# MAIN_SCH.net
KiCad netlist of a schematic drawn in Altium Designer
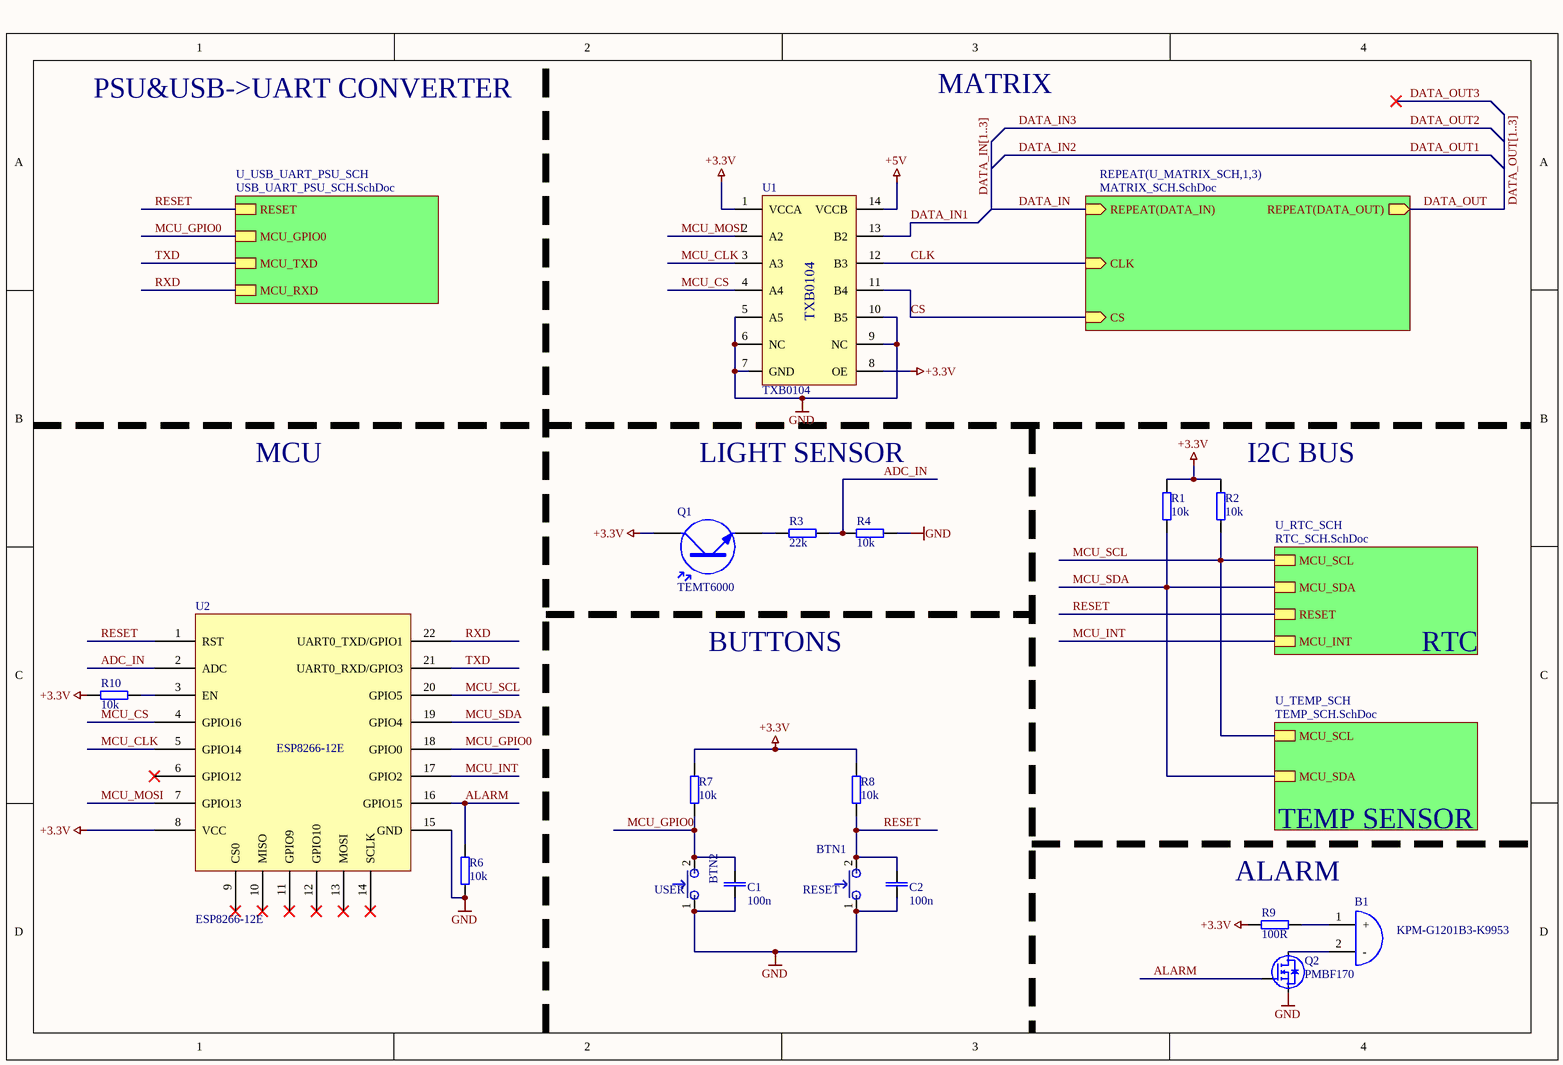
[diagram p0: MAIN_SCH.SchDoc]

(export (version "E")
  (design (tool "Eeschema 10.0.6"))
  (components
    (comp (ref "B1")
      (value "KPM-G1201B3-K9953")
      (footprint "KPM-G1201B3-K9953")
      (description "BUZZER")
      (libsource (lib "SCH_LIB") (part "BUZZER"))
    )
    (comp (ref "BTN1")
      (value "USER")
      (footprint "PBUTTON_SMD")
      (description "Tactile push button")
      (libsource (lib "SCH_LIB") (part "PUSHBUTTON"))
    )
    (comp (ref "BTN2")
      (value "RESET")
      (footprint "PBUTTON_SMD")
      (description "Tactile push button")
      (libsource (lib "SCH_LIB") (part "PUSHBUTTON"))
    )
    (comp (ref "C1")
      (value "100n")
      (footprint "CAP 0805")
      (description "NON POLARIZED CAPACITOR")
      (libsource (lib "SCH_LIB") (part "CAP"))
    )
    (comp (ref "C2")
      (value "100n")
      (footprint "CAP 0805")
      (description "NON POLARIZED CAPACITOR")
      (libsource (lib "SCH_LIB") (part "CAP"))
    )
    (comp (ref "Q1")
      (value "TEMT6000")
      (footprint "TEMT600")
      (description "Light sensor")
      (libsource (lib "SCH_LIB") (part "TEMT6000"))
    )
    (comp (ref "Q2")
      (value "PMBF170")
      (footprint "SOT23")
      (description "N-Channel MOSFET")
      (libsource (lib "SCH_LIB") (part "PMBF170"))
    )
    (comp (ref "R1")
      (value "10k")
      (footprint "RES 0805")
      (description "RESISTOR")
      (libsource (lib "SCH_LIB") (part "RES"))
    )
    (comp (ref "R2")
      (value "10k")
      (footprint "RES 0805")
      (description "RESISTOR")
      (libsource (lib "SCH_LIB") (part "RES"))
    )
    (comp (ref "R3")
      (value "22k")
      (footprint "RES 0805")
      (description "RESISTOR")
      (libsource (lib "") (part "RES_2"))
    )
    (comp (ref "R4")
      (value "10k")
      (footprint "RES 0805")
      (description "RESISTOR")
      (libsource (lib "") (part "RES_2"))
    )
    (comp (ref "R6")
      (value "10k")
      (footprint "RES 0805")
      (description "RESISTOR")
      (libsource (lib "SCH_LIB") (part "RES"))
    )
    (comp (ref "R7")
      (value "10k")
      (footprint "RES 0805")
      (description "RESISTOR")
      (libsource (lib "SCH_LIB") (part "RES"))
    )
    (comp (ref "R8")
      (value "10k")
      (footprint "RES 0805")
      (description "RESISTOR")
      (libsource (lib "SCH_LIB") (part "RES"))
    )
    (comp (ref "R9")
      (value "100R")
      (footprint "RES 0805")
      (description "RESISTOR")
      (libsource (lib "") (part "RES_2"))
    )
    (comp (ref "R10")
      (value "10k")
      (footprint "RES 0805")
      (description "RESISTOR")
      (libsource (lib "") (part "RES_1"))
    )
    (comp (ref "U1")
      (value "TXB0104")
      (footprint "SO14")
      (description "Voltage level shifter")
      (libsource (lib "SCH_LIB") (part "TXB0104"))
    )
    (comp (ref "U2")
      (value "ESP8266-12E")
      (footprint "ESP8266-12E")
      (description "WiFi module")
      (libsource (lib "SCH_LIB") (part "ESP8266-12E"))
    )
  )
  (nets
    (net (code "1") (name "+3.3V") (class "Default")
      (node (ref "Q1") (pin "1") (pinfunction "C_1") (pintype "passive"))
      (node (ref "R1") (pin "2") (pinfunction "2_2") (pintype "passive"))
      (node (ref "R10") (pin "2") (pinfunction "2_2") (pintype "passive"))
      (node (ref "R2") (pin "2") (pinfunction "2_2") (pintype "passive"))
      (node (ref "R7") (pin "2") (pinfunction "2_2") (pintype "passive"))
      (node (ref "R8") (pin "2") (pinfunction "2_2") (pintype "passive"))
      (node (ref "R9") (pin "1") (pinfunction "1_1") (pintype "passive"))
      (node (ref "U1") (pin "1") (pinfunction "VCCA_1") (pintype "passive"))
      (node (ref "U1") (pin "8") (pinfunction "OE_8") (pintype "passive"))
      (node (ref "U2") (pin "8") (pinfunction "VCC_8") (pintype "passive"))
    )
    (net (code "2") (name "+5V") (class "Default")
      (node (ref "U1") (pin "14") (pinfunction "VCCB_14") (pintype "passive"))
    )
    (net (code "3") (name "/ADC_IN") (class "Default")
      (node (ref "R3") (pin "2") (pinfunction "2_2") (pintype "passive"))
      (node (ref "R4") (pin "1") (pinfunction "1_1") (pintype "passive"))
      (node (ref "U2") (pin "2") (pinfunction "ADC_2") (pintype "passive"))
    )
    (net (code "4") (name "/ALARM") (class "Default")
      (node (ref "Q2") (pin "1") (pinfunction "G_1") (pintype "passive"))
      (node (ref "R6") (pin "2") (pinfunction "2_2") (pintype "passive"))
      (node (ref "U2") (pin "16") (pinfunction "GPIO15_16") (pintype "passive"))
    )
    (net (code "5") (name "/CLK") (class "Default")
      (node (ref "U1") (pin "12") (pinfunction "B3_12") (pintype "passive"))
    )
    (net (code "6") (name "/CS") (class "Default")
      (node (ref "U1") (pin "11") (pinfunction "B4_11") (pintype "passive"))
    )
    (net (code "8") (name "/DATA_IN1") (class "Default")
      (node (ref "U1") (pin "13") (pinfunction "B2_13") (pintype "passive"))
    )
    (net (code "15") (name "/MCU_CLK") (class "Default")
      (node (ref "U1") (pin "3") (pinfunction "A3_3") (pintype "passive"))
      (node (ref "U2") (pin "5") (pinfunction "GPIO14_5") (pintype "passive"))
    )
    (net (code "16") (name "/MCU_CS") (class "Default")
      (node (ref "U1") (pin "4") (pinfunction "A4_4") (pintype "passive"))
      (node (ref "U2") (pin "4") (pinfunction "GPIO16_4") (pintype "passive"))
    )
    (net (code "17") (name "/MCU_GPIO0") (class "Default")
      (node (ref "BTN2") (pin "2") (pintype "passive"))
      (node (ref "C1") (pin "2") (pinfunction "2_2") (pintype "passive"))
      (node (ref "R7") (pin "1") (pinfunction "1_1") (pintype "passive"))
      (node (ref "U2") (pin "18") (pinfunction "GPIO0_18") (pintype "passive"))
    )
    (net (code "18") (name "/MCU_INT") (class "Default")
      (node (ref "U2") (pin "17") (pinfunction "GPIO2_17") (pintype "passive"))
    )
    (net (code "19") (name "/MCU_MOSI") (class "Default")
      (node (ref "U1") (pin "2") (pinfunction "A2_2") (pintype "passive"))
      (node (ref "U2") (pin "7") (pinfunction "GPIO13_7") (pintype "passive"))
    )
    (net (code "20") (name "/MCU_SCL") (class "Default")
      (node (ref "R2") (pin "1") (pinfunction "1_1") (pintype "passive"))
      (node (ref "U2") (pin "20") (pinfunction "GPIO5_20") (pintype "passive"))
    )
    (net (code "21") (name "/MCU_SDA") (class "Default")
      (node (ref "R1") (pin "1") (pinfunction "1_1") (pintype "passive"))
      (node (ref "U2") (pin "19") (pinfunction "GPIO4_19") (pintype "passive"))
    )
    (net (code "22") (name "/RESET") (class "Default")
      (node (ref "BTN1") (pin "2") (pintype "passive"))
      (node (ref "C2") (pin "2") (pinfunction "2_2") (pintype "passive"))
      (node (ref "R8") (pin "1") (pinfunction "1_1") (pintype "passive"))
      (node (ref "U2") (pin "1") (pinfunction "RST_1") (pintype "passive"))
    )
    (net (code "23") (name "/RXD") (class "Default")
      (node (ref "U2") (pin "22") (pinfunction "UART0_TXD/GPIO1_22") (pintype "passive"))
    )
    (net (code "24") (name "/TXD") (class "Default")
      (node (ref "U2") (pin "21") (pinfunction "UART0_RXD/GPIO3_21") (pintype "passive"))
    )
    (net (code "25") (name "GND") (class "Default")
      (node (ref "BTN1") (pin "1") (pintype "passive"))
      (node (ref "BTN2") (pin "1") (pintype "passive"))
      (node (ref "C1") (pin "1") (pinfunction "1_1") (pintype "passive"))
      (node (ref "C2") (pin "1") (pinfunction "1_1") (pintype "passive"))
      (node (ref "Q2") (pin "2") (pinfunction "S_2") (pintype "passive"))
      (node (ref "R4") (pin "2") (pinfunction "2_2") (pintype "passive"))
      (node (ref "R6") (pin "1") (pinfunction "1_1") (pintype "passive"))
      (node (ref "U1") (pin "10") (pinfunction "B5_10") (pintype "passive"))
      (node (ref "U1") (pin "5") (pinfunction "A5_5") (pintype "passive"))
      (node (ref "U1") (pin "6") (pinfunction "NC_6") (pintype "passive"))
      (node (ref "U1") (pin "7") (pinfunction "GND_7") (pintype "passive"))
      (node (ref "U1") (pin "9") (pinfunction "NC_9") (pintype "passive"))
      (node (ref "U2") (pin "15") (pinfunction "GND_15") (pintype "passive"))
    )
    (net (code "26") (name "Net-(B1-+)") (class "Default")
      (node (ref "B1") (pin "1") (pinfunction "+_1") (pintype "passive"))
      (node (ref "R9") (pin "2") (pinfunction "2_2") (pintype "passive"))
    )
    (net (code "27") (name "Net-(B1--)") (class "Default")
      (node (ref "B1") (pin "2") (pinfunction "-_2") (pintype "passive"))
      (node (ref "Q2") (pin "3") (pinfunction "D_3") (pintype "passive"))
    )
    (net (code "28") (name "Net-(Q1-E)") (class "Default")
      (node (ref "Q1") (pin "2") (pinfunction "E_2") (pintype "passive"))
      (node (ref "R3") (pin "1") (pinfunction "1_1") (pintype "passive"))
    )
    (net (code "29") (name "Net-(U2-EN)") (class "Default")
      (node (ref "R10") (pin "1") (pinfunction "1_1") (pintype "passive"))
      (node (ref "U2") (pin "3") (pinfunction "EN_3") (pintype "passive"))
    )
    (net (code "30") (name "unconnected-(U2-CS0-Pad9)") (class "Default")
      (node (ref "U2") (pin "9") (pinfunction "CS0_9") (pintype "passive+no_connect"))
    )
    (net (code "31") (name "unconnected-(U2-GPIO9-Pad11)") (class "Default")
      (node (ref "U2") (pin "11") (pinfunction "GPIO9_11") (pintype "passive+no_connect"))
    )
    (net (code "32") (name "unconnected-(U2-GPIO10-Pad12)") (class "Default")
      (node (ref "U2") (pin "12") (pinfunction "GPIO10_12") (pintype "passive+no_connect"))
    )
    (net (code "33") (name "unconnected-(U2-GPIO12-Pad6)") (class "Default")
      (node (ref "U2") (pin "6") (pinfunction "GPIO12_6") (pintype "passive+no_connect"))
    )
    (net (code "34") (name "unconnected-(U2-MISO-Pad10)") (class "Default")
      (node (ref "U2") (pin "10") (pinfunction "MISO_10") (pintype "passive+no_connect"))
    )
    (net (code "35") (name "unconnected-(U2-MOSI-Pad13)") (class "Default")
      (node (ref "U2") (pin "13") (pinfunction "MOSI_13") (pintype "passive+no_connect"))
    )
    (net (code "36") (name "unconnected-(U2-SCLK-Pad14)") (class "Default")
      (node (ref "U2") (pin "14") (pinfunction "SCLK_14") (pintype "passive+no_connect"))
    )
  )
)
